# BeamerCtrl.net
KiCad netlist of a schematic drawn in EAGLE
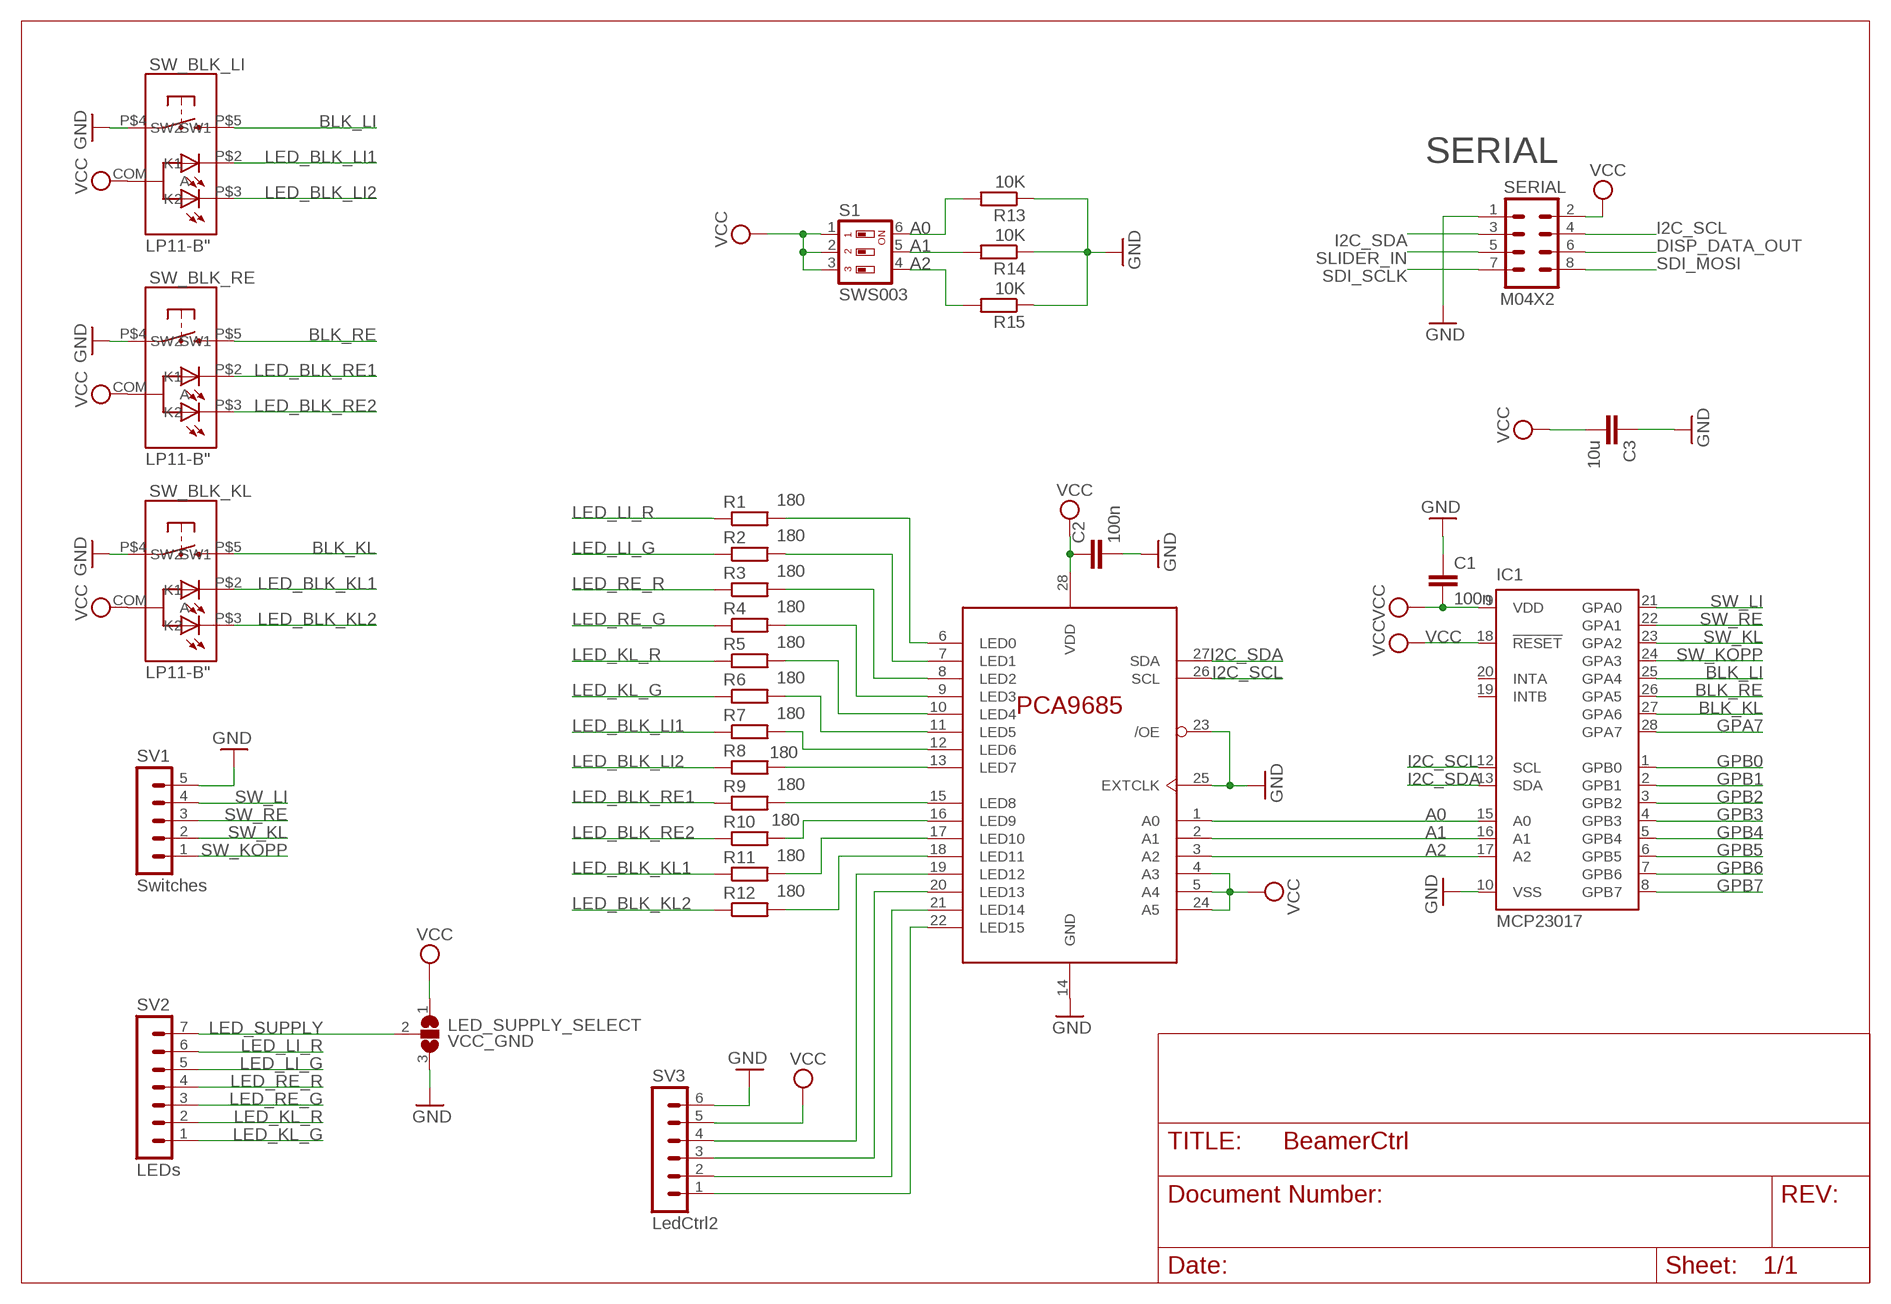
[diagram p0: schematic, sheet 1]

(export (version "E")
  (design (tool "Eeschema 10.0.6"))
  (components
    (comp (ref "C1")
      (value "100n")
      (footprint "eagle-import:C0603")
      (libsource (lib "eagle-import") (part "C-EUC0603"))
    )
    (comp (ref "C2")
      (value "100n")
      (footprint "eagle-import:C0603")
      (libsource (lib "eagle-import") (part "C-EUC0603"))
    )
    (comp (ref "C3")
      (value "10u")
      (footprint "eagle-import:C0805")
      (libsource (lib "eagle-import") (part "C-EUC0805"))
    )
    (comp (ref "IC1")
      (value "MCP23017")
      (footprint "eagle-import:SSOP28")
      (fields (field (name "MF") "MICROCHIP") (field (name "MPN") "MCP23017-E/SS"))
      (libsource (lib "eagle-import") (part "MCP23017SS"))
    )
    (comp (ref "IC2")
      (value "PCA9685PW")
      (footprint "eagle-import:TSSOP28")
      (libsource (lib "eagle-import") (part "PCA9685PW"))
    )
    (comp (ref "LED_SUPPLY_SELECT")
      (value "VCC_GND")
      (footprint "eagle-import:SJ_2")
      (libsource (lib "eagle-import") (part "SJ2W"))
    )
    (comp (ref "R1")
      (value "180")
      (footprint "eagle-import:R0603")
      (libsource (lib "eagle-import") (part "R-EU_R0603"))
    )
    (comp (ref "R2")
      (value "180")
      (footprint "eagle-import:R0603")
      (libsource (lib "eagle-import") (part "R-EU_R0603"))
    )
    (comp (ref "R3")
      (value "180")
      (footprint "eagle-import:R0603")
      (libsource (lib "eagle-import") (part "R-EU_R0603"))
    )
    (comp (ref "R4")
      (value "180")
      (footprint "eagle-import:R0603")
      (libsource (lib "eagle-import") (part "R-EU_R0603"))
    )
    (comp (ref "R5")
      (value "180")
      (footprint "eagle-import:R0603")
      (libsource (lib "eagle-import") (part "R-EU_R0603"))
    )
    (comp (ref "R6")
      (value "180")
      (footprint "eagle-import:R0603")
      (libsource (lib "eagle-import") (part "R-EU_R0603"))
    )
    (comp (ref "R7")
      (value "180")
      (footprint "eagle-import:R0603")
      (libsource (lib "eagle-import") (part "R-EU_R0603"))
    )
    (comp (ref "R8")
      (value "180")
      (footprint "eagle-import:R0603")
      (libsource (lib "eagle-import") (part "R-EU_R0603"))
    )
    (comp (ref "R9")
      (value "180")
      (footprint "eagle-import:R0603")
      (libsource (lib "eagle-import") (part "R-EU_R0603"))
    )
    (comp (ref "R10")
      (value "180")
      (footprint "eagle-import:R0603")
      (libsource (lib "eagle-import") (part "R-EU_R0603"))
    )
    (comp (ref "R11")
      (value "180")
      (footprint "eagle-import:R0603")
      (libsource (lib "eagle-import") (part "R-EU_R0603"))
    )
    (comp (ref "R12")
      (value "180")
      (footprint "eagle-import:R0603")
      (libsource (lib "eagle-import") (part "R-EU_R0603"))
    )
    (comp (ref "R13")
      (value "10K")
      (footprint "eagle-import:R0603")
      (libsource (lib "eagle-import") (part "R-EU_R0603"))
    )
    (comp (ref "R14")
      (value "10K")
      (footprint "eagle-import:R0603")
      (libsource (lib "eagle-import") (part "R-EU_R0603"))
    )
    (comp (ref "R15")
      (value "10K")
      (footprint "eagle-import:R0603")
      (libsource (lib "eagle-import") (part "R-EU_R0603"))
    )
    (comp (ref "S1")
      (value "SWS003")
      (footprint "eagle-import:SMS-003")
      (libsource (lib "eagle-import") (part "SWS003"))
    )
    (comp (ref "SERIAL")
      (value "M04X2")
      (footprint "eagle-import:2X4")
      (libsource (lib "eagle-import") (part "M04X2"))
    )
    (comp (ref "SV1")
      (value "Switches")
      (footprint "eagle-import:MA05-1")
      (libsource (lib "eagle-import") (part "MA05-1"))
    )
    (comp (ref "SV2")
      (value "LEDs")
      (footprint "eagle-import:MA07-1")
      (libsource (lib "eagle-import") (part "MA07-1"))
    )
    (comp (ref "SV3")
      (value "LedCtrl2")
      (footprint "eagle-import:MA06-1")
      (libsource (lib "eagle-import") (part "MA06-1"))
    )
    (comp (ref "SW_BLK_KL")
      (value "LP11-B\"")
      (footprint "eagle-import:LP11")
      (libsource (lib "eagle-import") (part "LP11-B{dblquote}"))
    )
    (comp (ref "SW_BLK_LI")
      (value "LP11-B\"")
      (footprint "eagle-import:LP11")
      (libsource (lib "eagle-import") (part "LP11-B{dblquote}"))
    )
    (comp (ref "SW_BLK_RE")
      (value "LP11-B\"")
      (footprint "eagle-import:LP11")
      (libsource (lib "eagle-import") (part "LP11-B{dblquote}"))
    )
  )
  (nets
    (net (code "1") (name "/A0") (class "Default")
      (node (ref "IC1") (pin "15") (pinfunction "A0_15") (pintype "input"))
      (node (ref "IC2") (pin "1") (pinfunction "A0_1") (pintype "bidirectional"))
      (node (ref "R13") (pin "2") (pinfunction "2_2") (pintype "passive"))
      (node (ref "S1") (pin "6") (pinfunction "6_6") (pintype "passive"))
    )
    (net (code "2") (name "/A1") (class "Default")
      (node (ref "IC1") (pin "16") (pinfunction "A1_16") (pintype "input"))
      (node (ref "IC2") (pin "2") (pinfunction "A1_2") (pintype "bidirectional"))
      (node (ref "R14") (pin "2") (pinfunction "2_2") (pintype "passive"))
      (node (ref "S1") (pin "5") (pinfunction "5_5") (pintype "passive"))
    )
    (net (code "3") (name "/A2") (class "Default")
      (node (ref "IC1") (pin "17") (pinfunction "A2_17") (pintype "input"))
      (node (ref "IC2") (pin "3") (pinfunction "A2_3") (pintype "bidirectional"))
      (node (ref "R15") (pin "2") (pinfunction "2_2") (pintype "passive"))
      (node (ref "S1") (pin "4") (pinfunction "4_4") (pintype "passive"))
    )
    (net (code "4") (name "/BLK_KL") (class "Default")
      (node (ref "IC1") (pin "27") (pinfunction "GPA6_27") (pintype "bidirectional"))
      (node (ref "SW_BLK_KL") (pin "P$5") (pinfunction "SW2_P$5") (pintype "bidirectional"))
    )
    (net (code "5") (name "/BLK_LI") (class "Default")
      (node (ref "IC1") (pin "25") (pinfunction "GPA4_25") (pintype "bidirectional"))
      (node (ref "SW_BLK_LI") (pin "P$5") (pinfunction "SW2_P$5") (pintype "bidirectional"))
    )
    (net (code "6") (name "/BLK_RE") (class "Default")
      (node (ref "IC1") (pin "26") (pinfunction "GPA5_26") (pintype "bidirectional"))
      (node (ref "SW_BLK_RE") (pin "P$5") (pinfunction "SW2_P$5") (pintype "bidirectional"))
    )
    (net (code "7") (name "/DISP_DATA_OUT") (class "Default")
      (node (ref "SERIAL") (pin "6") (pinfunction "6_6") (pintype "passive"))
    )
    (net (code "8") (name "/GPA7") (class "Default")
      (node (ref "IC1") (pin "28") (pinfunction "GPA7_28") (pintype "bidirectional"))
    )
    (net (code "9") (name "/GPB0") (class "Default")
      (node (ref "IC1") (pin "1") (pinfunction "GPB0_1") (pintype "bidirectional"))
    )
    (net (code "10") (name "/GPB1") (class "Default")
      (node (ref "IC1") (pin "2") (pinfunction "GPB1_2") (pintype "bidirectional"))
    )
    (net (code "11") (name "/GPB2") (class "Default")
      (node (ref "IC1") (pin "3") (pinfunction "GPB2_3") (pintype "bidirectional"))
    )
    (net (code "12") (name "/GPB3") (class "Default")
      (node (ref "IC1") (pin "4") (pinfunction "GPB3_4") (pintype "bidirectional"))
    )
    (net (code "13") (name "/GPB4") (class "Default")
      (node (ref "IC1") (pin "5") (pinfunction "GPB4_5") (pintype "bidirectional"))
    )
    (net (code "14") (name "/GPB5") (class "Default")
      (node (ref "IC1") (pin "6") (pinfunction "GPB5_6") (pintype "bidirectional"))
    )
    (net (code "15") (name "/GPB6") (class "Default")
      (node (ref "IC1") (pin "7") (pinfunction "GPB6_7") (pintype "bidirectional"))
    )
    (net (code "16") (name "/GPB7") (class "Default")
      (node (ref "IC1") (pin "8") (pinfunction "GPB7_8") (pintype "bidirectional"))
    )
    (net (code "17") (name "/I2C_SCL") (class "Default")
      (node (ref "IC1") (pin "12") (pinfunction "SCL_12") (pintype "input"))
      (node (ref "IC2") (pin "26") (pinfunction "SCL_26") (pintype "bidirectional"))
      (node (ref "SERIAL") (pin "4") (pinfunction "4_4") (pintype "passive"))
    )
    (net (code "18") (name "/I2C_SDA") (class "Default")
      (node (ref "IC1") (pin "13") (pinfunction "SDA_13") (pintype "bidirectional"))
      (node (ref "IC2") (pin "27") (pinfunction "SDA_27") (pintype "bidirectional"))
      (node (ref "SERIAL") (pin "3") (pinfunction "3_3") (pintype "passive"))
    )
    (net (code "19") (name "/LED_BLK_KL1") (class "Default")
      (node (ref "R11") (pin "1") (pinfunction "1_1") (pintype "passive"))
      (node (ref "SW_BLK_KL") (pin "P$2") (pinfunction "K1_P$2") (pintype "bidirectional"))
    )
    (net (code "20") (name "/LED_BLK_KL2") (class "Default")
      (node (ref "R12") (pin "1") (pinfunction "1_1") (pintype "passive"))
      (node (ref "SW_BLK_KL") (pin "P$3") (pinfunction "K2_P$3") (pintype "bidirectional"))
    )
    (net (code "21") (name "/LED_BLK_LI1") (class "Default")
      (node (ref "R7") (pin "1") (pinfunction "1_1") (pintype "passive"))
      (node (ref "SW_BLK_LI") (pin "P$2") (pinfunction "K1_P$2") (pintype "bidirectional"))
    )
    (net (code "22") (name "/LED_BLK_LI2") (class "Default")
      (node (ref "R8") (pin "1") (pinfunction "1_1") (pintype "passive"))
      (node (ref "SW_BLK_LI") (pin "P$3") (pinfunction "K2_P$3") (pintype "bidirectional"))
    )
    (net (code "23") (name "/LED_BLK_RE1") (class "Default")
      (node (ref "R9") (pin "1") (pinfunction "1_1") (pintype "passive"))
      (node (ref "SW_BLK_RE") (pin "P$2") (pinfunction "K1_P$2") (pintype "bidirectional"))
    )
    (net (code "24") (name "/LED_BLK_RE2") (class "Default")
      (node (ref "R10") (pin "1") (pinfunction "1_1") (pintype "passive"))
      (node (ref "SW_BLK_RE") (pin "P$3") (pinfunction "K2_P$3") (pintype "bidirectional"))
    )
    (net (code "25") (name "/LED_KL_G") (class "Default")
      (node (ref "R6") (pin "1") (pinfunction "1_1") (pintype "passive"))
      (node (ref "SV2") (pin "1") (pinfunction "1_1") (pintype "passive"))
    )
    (net (code "26") (name "/LED_KL_R") (class "Default")
      (node (ref "R5") (pin "1") (pinfunction "1_1") (pintype "passive"))
      (node (ref "SV2") (pin "2") (pinfunction "2_2") (pintype "passive"))
    )
    (net (code "27") (name "/LED_LI_G") (class "Default")
      (node (ref "R2") (pin "1") (pinfunction "1_1") (pintype "passive"))
      (node (ref "SV2") (pin "5") (pinfunction "5_5") (pintype "passive"))
    )
    (net (code "28") (name "/LED_LI_R") (class "Default")
      (node (ref "R1") (pin "1") (pinfunction "1_1") (pintype "passive"))
      (node (ref "SV2") (pin "6") (pinfunction "6_6") (pintype "passive"))
    )
    (net (code "29") (name "/LED_RE_G") (class "Default")
      (node (ref "R4") (pin "1") (pinfunction "1_1") (pintype "passive"))
      (node (ref "SV2") (pin "3") (pinfunction "3_3") (pintype "passive"))
    )
    (net (code "30") (name "/LED_RE_R") (class "Default")
      (node (ref "R3") (pin "1") (pinfunction "1_1") (pintype "passive"))
      (node (ref "SV2") (pin "4") (pinfunction "4_4") (pintype "passive"))
    )
    (net (code "31") (name "/LED_SUPPLY") (class "Default")
      (node (ref "LED_SUPPLY_SELECT") (pin "2") (pinfunction "2_2") (pintype "passive"))
      (node (ref "SV2") (pin "7") (pinfunction "7_7") (pintype "passive"))
    )
    (net (code "32") (name "/SDI_MOSI") (class "Default")
      (node (ref "SERIAL") (pin "8") (pinfunction "8_8") (pintype "passive"))
    )
    (net (code "33") (name "/SDI_SCLK") (class "Default")
      (node (ref "SERIAL") (pin "7") (pinfunction "7_7") (pintype "passive"))
    )
    (net (code "34") (name "/SLIDER_IN") (class "Default")
      (node (ref "SERIAL") (pin "5") (pinfunction "5_5") (pintype "passive"))
    )
    (net (code "35") (name "/SW_KL") (class "Default")
      (node (ref "IC1") (pin "23") (pinfunction "GPA2_23") (pintype "bidirectional"))
      (node (ref "SV1") (pin "2") (pinfunction "2_2") (pintype "passive"))
    )
    (net (code "36") (name "/SW_KOPP") (class "Default")
      (node (ref "IC1") (pin "24") (pinfunction "GPA3_24") (pintype "bidirectional"))
      (node (ref "SV1") (pin "1") (pinfunction "1_1") (pintype "passive"))
    )
    (net (code "37") (name "/SW_LI") (class "Default")
      (node (ref "IC1") (pin "21") (pinfunction "GPA0_21") (pintype "bidirectional"))
      (node (ref "SV1") (pin "4") (pinfunction "4_4") (pintype "passive"))
    )
    (net (code "38") (name "/SW_RE") (class "Default")
      (node (ref "IC1") (pin "22") (pinfunction "GPA1_22") (pintype "bidirectional"))
      (node (ref "SV1") (pin "3") (pinfunction "3_3") (pintype "passive"))
    )
    (net (code "39") (name "GND") (class "Default")
      (node (ref "C1") (pin "1") (pinfunction "1_1") (pintype "passive"))
      (node (ref "C2") (pin "2") (pinfunction "2_2") (pintype "passive"))
      (node (ref "C3") (pin "1") (pinfunction "1_1") (pintype "passive"))
      (node (ref "IC1") (pin "10") (pinfunction "VSS_10") (pintype "power_in"))
      (node (ref "IC2") (pin "14") (pinfunction "GND_14") (pintype "power_in"))
      (node (ref "IC2") (pin "23") (pinfunction "/OE_23") (pintype "bidirectional"))
      (node (ref "IC2") (pin "25") (pinfunction "EXTCLK_25") (pintype "input"))
      (node (ref "LED_SUPPLY_SELECT") (pin "3") (pinfunction "3_3") (pintype "passive"))
      (node (ref "R13") (pin "1") (pinfunction "1_1") (pintype "passive"))
      (node (ref "R14") (pin "1") (pinfunction "1_1") (pintype "passive"))
      (node (ref "R15") (pin "1") (pinfunction "1_1") (pintype "passive"))
      (node (ref "SERIAL") (pin "1") (pinfunction "1_1") (pintype "passive"))
      (node (ref "SV1") (pin "5") (pinfunction "5_5") (pintype "passive"))
      (node (ref "SV3") (pin "6") (pinfunction "6_6") (pintype "passive"))
      (node (ref "SW_BLK_KL") (pin "P$4") (pinfunction "SW1_P$4") (pintype "bidirectional"))
      (node (ref "SW_BLK_LI") (pin "P$4") (pinfunction "SW1_P$4") (pintype "bidirectional"))
      (node (ref "SW_BLK_RE") (pin "P$4") (pinfunction "SW1_P$4") (pintype "bidirectional"))
    )
    (net (code "40") (name "Net-(IC2-LED0)") (class "Default")
      (node (ref "IC2") (pin "6") (pinfunction "LED0_6") (pintype "bidirectional"))
      (node (ref "R1") (pin "2") (pinfunction "2_2") (pintype "passive"))
    )
    (net (code "41") (name "Net-(IC2-LED1)") (class "Default")
      (node (ref "IC2") (pin "7") (pinfunction "LED1_7") (pintype "bidirectional"))
      (node (ref "R2") (pin "2") (pinfunction "2_2") (pintype "passive"))
    )
    (net (code "42") (name "Net-(IC2-LED2)") (class "Default")
      (node (ref "IC2") (pin "8") (pinfunction "LED2_8") (pintype "bidirectional"))
      (node (ref "R3") (pin "2") (pinfunction "2_2") (pintype "passive"))
    )
    (net (code "43") (name "Net-(IC2-LED3)") (class "Default")
      (node (ref "IC2") (pin "9") (pinfunction "LED3_9") (pintype "bidirectional"))
      (node (ref "R4") (pin "2") (pinfunction "2_2") (pintype "passive"))
    )
    (net (code "44") (name "Net-(IC2-LED4)") (class "Default")
      (node (ref "IC2") (pin "10") (pinfunction "LED4_10") (pintype "bidirectional"))
      (node (ref "R5") (pin "2") (pinfunction "2_2") (pintype "passive"))
    )
    (net (code "45") (name "Net-(IC2-LED5)") (class "Default")
      (node (ref "IC2") (pin "11") (pinfunction "LED5_11") (pintype "bidirectional"))
      (node (ref "R6") (pin "2") (pinfunction "2_2") (pintype "passive"))
    )
    (net (code "46") (name "Net-(IC2-LED6)") (class "Default")
      (node (ref "IC2") (pin "12") (pinfunction "LED6_12") (pintype "bidirectional"))
      (node (ref "R7") (pin "2") (pinfunction "2_2") (pintype "passive"))
    )
    (net (code "47") (name "Net-(IC2-LED7)") (class "Default")
      (node (ref "IC2") (pin "13") (pinfunction "LED7_13") (pintype "bidirectional"))
      (node (ref "R8") (pin "2") (pinfunction "2_2") (pintype "passive"))
    )
    (net (code "48") (name "Net-(IC2-LED8)") (class "Default")
      (node (ref "IC2") (pin "15") (pinfunction "LED8_15") (pintype "bidirectional"))
      (node (ref "R9") (pin "2") (pinfunction "2_2") (pintype "passive"))
    )
    (net (code "49") (name "Net-(IC2-LED9)") (class "Default")
      (node (ref "IC2") (pin "16") (pinfunction "LED9_16") (pintype "bidirectional"))
      (node (ref "R10") (pin "2") (pinfunction "2_2") (pintype "passive"))
    )
    (net (code "50") (name "Net-(IC2-LED10)") (class "Default")
      (node (ref "IC2") (pin "17") (pinfunction "LED10_17") (pintype "bidirectional"))
      (node (ref "R11") (pin "2") (pinfunction "2_2") (pintype "passive"))
    )
    (net (code "51") (name "Net-(IC2-LED11)") (class "Default")
      (node (ref "IC2") (pin "18") (pinfunction "LED11_18") (pintype "bidirectional"))
      (node (ref "R12") (pin "2") (pinfunction "2_2") (pintype "passive"))
    )
    (net (code "52") (name "Net-(IC2-LED12)") (class "Default")
      (node (ref "IC2") (pin "19") (pinfunction "LED12_19") (pintype "bidirectional"))
      (node (ref "SV3") (pin "4") (pinfunction "4_4") (pintype "passive"))
    )
    (net (code "53") (name "Net-(IC2-LED13)") (class "Default")
      (node (ref "IC2") (pin "20") (pinfunction "LED13_20") (pintype "bidirectional"))
      (node (ref "SV3") (pin "3") (pinfunction "3_3") (pintype "passive"))
    )
    (net (code "54") (name "Net-(IC2-LED14)") (class "Default")
      (node (ref "IC2") (pin "21") (pinfunction "LED14_21") (pintype "bidirectional"))
      (node (ref "SV3") (pin "2") (pinfunction "2_2") (pintype "passive"))
    )
    (net (code "55") (name "Net-(IC2-LED15)") (class "Default")
      (node (ref "IC2") (pin "22") (pinfunction "LED15_22") (pintype "bidirectional"))
      (node (ref "SV3") (pin "1") (pinfunction "1_1") (pintype "passive"))
    )
    (net (code "56") (name "VCC") (class "Default")
      (node (ref "C1") (pin "2") (pinfunction "2_2") (pintype "passive"))
      (node (ref "C2") (pin "1") (pinfunction "1_1") (pintype "passive"))
      (node (ref "C3") (pin "2") (pinfunction "2_2") (pintype "passive"))
      (node (ref "IC1") (pin "18") (pinfunction "~{RESET}_18") (pintype "input"))
      (node (ref "IC1") (pin "9") (pinfunction "VDD_9") (pintype "power_in"))
      (node (ref "IC2") (pin "24") (pinfunction "A5_24") (pintype "bidirectional"))
      (node (ref "IC2") (pin "28") (pinfunction "VDD_28") (pintype "power_in"))
      (node (ref "IC2") (pin "4") (pinfunction "A3_4") (pintype "bidirectional"))
      (node (ref "IC2") (pin "5") (pinfunction "A4_5") (pintype "bidirectional"))
      (node (ref "LED_SUPPLY_SELECT") (pin "1") (pinfunction "1_1") (pintype "passive"))
      (node (ref "S1") (pin "1") (pinfunction "1_1") (pintype "passive"))
      (node (ref "S1") (pin "2") (pinfunction "2_2") (pintype "passive"))
      (node (ref "S1") (pin "3") (pinfunction "3_3") (pintype "passive"))
      (node (ref "SERIAL") (pin "2") (pinfunction "2_2") (pintype "passive"))
      (node (ref "SV3") (pin "5") (pinfunction "5_5") (pintype "passive"))
      (node (ref "SW_BLK_KL") (pin "COM") (pinfunction "A_COM") (pintype "bidirectional"))
      (node (ref "SW_BLK_LI") (pin "COM") (pinfunction "A_COM") (pintype "bidirectional"))
      (node (ref "SW_BLK_RE") (pin "COM") (pinfunction "A_COM") (pintype "bidirectional"))
    )
    (net (code "57") (name "unconnected-(IC1-INTA-Pad20)") (class "Default")
      (node (ref "IC1") (pin "20") (pinfunction "INTA_20") (pintype "output"))
    )
    (net (code "58") (name "unconnected-(IC1-INTB-Pad19)") (class "Default")
      (node (ref "IC1") (pin "19") (pinfunction "INTB_19") (pintype "output"))
    )
  )
)
